# CSensor.net
KiCad netlist of a schematic drawn in Altium Designer
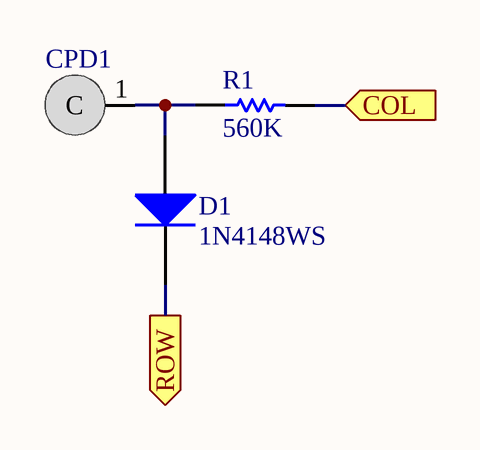
[diagram p0: CSensor.SchDoc]

(export (version "E")
  (design (tool "Eeschema 10.0.6"))
  (components
    (comp (ref "CPD1") (value "CPAD") (footprint "CPAD") (libsource (lib "Skumpad") (part "CPAD")))
    (comp (ref "D1")
      (value "1N4148WS")
      (footprint "DIOD-SOD123-2_V")
      (description "Fast Switching Diode, 100 V, 0.15 A, -65 to 150 degC, 2-Pin?SOD123, RoHS, Tape and Reel")
      (fields (field (name "MANUFACTURER") "DiodesIncorporated"))
      (libsource (lib "Altium Content Vault") (part "D-AK-2"))
    )
    (comp (ref "R1")
      (value "560K")
      (footprint "RESC1608X55X30NL15T15")
      (fields (field (name "MANUFACTURER") "Panasonic") (field (name "PART NUMBER") "ERJ3EKF5603V"))
      (libsource (lib "Altium Content Vault") (part "RES"))
    )
  )
  (nets
    (net (code "1") (name "/COL") (class "Default")
      (node (ref "R1") (pin "2") (pinfunction "2_2") (pintype "passive"))
    )
    (net (code "2") (name "/ROW") (class "Default")
      (node (ref "D1") (pin "2") (pinfunction "K_2") (pintype "passive"))
    )
    (net (code "3") (name "Net-(D1-A)") (class "Default")
      (node (ref "CPD1") (pin "1") (pintype "power_in"))
      (node (ref "D1") (pin "1") (pinfunction "A_1") (pintype "passive"))
      (node (ref "R1") (pin "1") (pinfunction "1_1") (pintype "passive"))
    )
  )
)
